# pi_zero.net
KiCad netlist of a schematic drawn in EAGLE
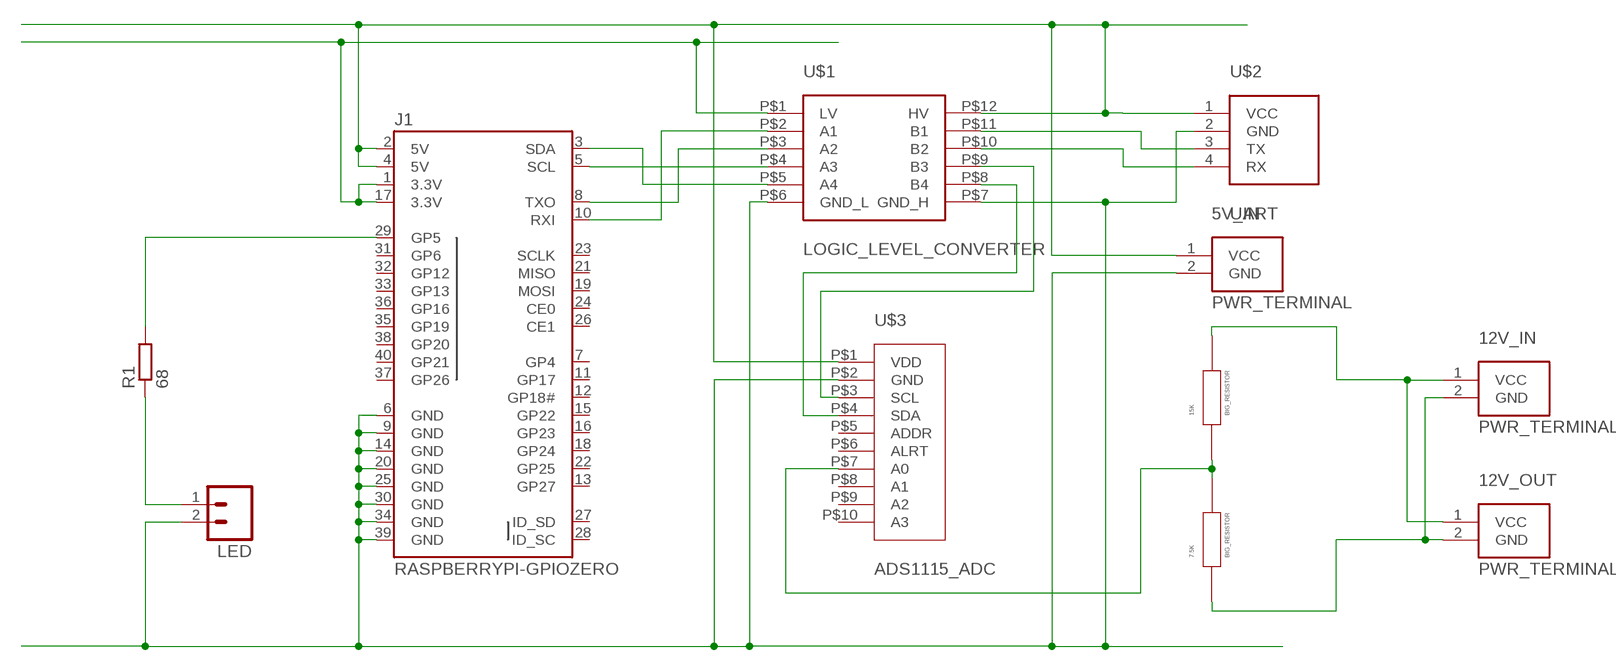
[diagram p0: schematic, sheet 1]

(export (version "E")
  (design (tool "Eeschema 10.0.6"))
  (components
    (comp (ref "5V_IN")
      (value "PWR_TERMINAL")
      (footprint "eagle-import:PWR_TERMINAL")
      (libsource (lib "eagle-import") (part "PWR_TERMINAL"))
    )
    (comp (ref "7.5K")
      (value "BIG_RESISTOR")
      (footprint "eagle-import:BIG_RESISTOR")
      (libsource (lib "eagle-import") (part "BIG_RESISTOR"))
    )
    (comp (ref "12V_IN")
      (value "PWR_TERMINAL")
      (footprint "eagle-import:PWR_TERMINAL")
      (libsource (lib "eagle-import") (part "PWR_TERMINAL"))
    )
    (comp (ref "12V_OUT")
      (value "PWR_TERMINAL")
      (footprint "eagle-import:PWR_TERMINAL")
      (libsource (lib "eagle-import") (part "PWR_TERMINAL"))
    )
    (comp (ref "15K")
      (value "BIG_RESISTOR")
      (footprint "eagle-import:BIG_RESISTOR")
      (libsource (lib "eagle-import") (part "BIG_RESISTOR"))
    )
    (comp (ref "J1")
      (value "RASPBERRYPI-GPIOZERO")
      (footprint "eagle-import:2X20-ZERO")
      (libsource (lib "eagle-import") (part "RASPBERRYPI-GPIOZERO"))
    )
    (comp (ref "LED")
      (value "M02LOCK_LONGPADS")
      (footprint "eagle-import:1X02_LOCK_LONGPADS")
      (libsource (lib "eagle-import") (part "M02LOCK_LONGPADS"))
    )
    (comp (ref "R1")
      (value "68")
      (footprint "eagle-import:0204_7")
      (libsource (lib "eagle-import") (part "R-EU_0204/7"))
    )
    (comp (ref "U$1")
      (value "LOGIC_LEVEL_CONVERTER")
      (footprint "eagle-import:LOGIC_LEVEL_CONVERTER")
      (libsource (lib "eagle-import") (part "LOGIC_LEVEL_CONVERTER"))
    )
    (comp (ref "U$2")
      (value "UART")
      (footprint "eagle-import:I2C_TERM")
      (libsource (lib "eagle-import") (part "UART"))
    )
    (comp (ref "U$3")
      (value "ADS1115_ADC")
      (footprint "eagle-import:ADS1115_ADC")
      (libsource (lib "eagle-import") (part "ADS1115_ADC"))
    )
  )
  (nets
    (net (code "1") (name "Net-(5V_IN-GND)") (class "Default")
      (node (ref "5V_IN") (pin "2") (pinfunction "GND_2") (pintype "bidirectional"))
      (node (ref "J1") (pin "14") (pinfunction "GND_14") (pintype "power_in"))
      (node (ref "J1") (pin "20") (pinfunction "GND_20") (pintype "power_in"))
      (node (ref "J1") (pin "25") (pinfunction "GND_25") (pintype "power_in"))
      (node (ref "J1") (pin "30") (pinfunction "GND_30") (pintype "power_in"))
      (node (ref "J1") (pin "34") (pinfunction "GND_34") (pintype "power_in"))
      (node (ref "J1") (pin "39") (pinfunction "GND_39") (pintype "power_in"))
      (node (ref "J1") (pin "6") (pinfunction "GND_6") (pintype "power_in"))
      (node (ref "J1") (pin "9") (pinfunction "GND_9") (pintype "power_in"))
      (node (ref "LED") (pin "2") (pinfunction "2_2") (pintype "passive"))
      (node (ref "U$1") (pin "P$6") (pinfunction "GND_L_P$6") (pintype "bidirectional"))
      (node (ref "U$1") (pin "P$7") (pinfunction "GND_H_P$7") (pintype "bidirectional"))
      (node (ref "U$2") (pin "2") (pinfunction "GND_2") (pintype "bidirectional"))
      (node (ref "U$3") (pin "P$2") (pinfunction "GND_P$2") (pintype "bidirectional"))
    )
    (net (code "2") (name "Net-(5V_IN-VCC)") (class "Default")
      (node (ref "5V_IN") (pin "1") (pinfunction "VCC_1") (pintype "bidirectional"))
      (node (ref "J1") (pin "2") (pinfunction "5V_2") (pintype "power_in"))
      (node (ref "J1") (pin "4") (pinfunction "5V_4") (pintype "power_in"))
      (node (ref "U$1") (pin "P$12") (pinfunction "HV_P$12") (pintype "bidirectional"))
      (node (ref "U$2") (pin "1") (pinfunction "VCC_1") (pintype "bidirectional"))
      (node (ref "U$3") (pin "P$1") (pinfunction "VDD_P$1") (pintype "bidirectional"))
    )
    (net (code "3") (name "Net-(12V_IN-GND)") (class "Default")
      (node (ref "12V_IN") (pin "2") (pinfunction "GND_2") (pintype "bidirectional"))
      (node (ref "12V_OUT") (pin "2") (pinfunction "GND_2") (pintype "bidirectional"))
      (node (ref "7.5K") (pin "P$1") (pinfunction "P$1_P$1") (pintype "bidirectional"))
    )
    (net (code "4") (name "Net-(12V_IN-VCC)") (class "Default")
      (node (ref "12V_IN") (pin "1") (pinfunction "VCC_1") (pintype "bidirectional"))
      (node (ref "12V_OUT") (pin "1") (pinfunction "VCC_1") (pintype "bidirectional"))
      (node (ref "15K") (pin "P$2") (pinfunction "P$2_P$2") (pintype "bidirectional"))
    )
    (net (code "5") (name "Net-(J1-GP5)") (class "Default")
      (node (ref "J1") (pin "29") (pinfunction "GP5_29") (pintype "bidirectional"))
      (node (ref "R1") (pin "2") (pinfunction "2_2") (pintype "passive"))
    )
    (net (code "6") (name "Net-(J1-RXI)") (class "Default")
      (node (ref "J1") (pin "10") (pinfunction "RXI_10") (pintype "input"))
      (node (ref "U$1") (pin "P$2") (pinfunction "A1_P$2") (pintype "bidirectional"))
    )
    (net (code "7") (name "Net-(J1-SCL)") (class "Default")
      (node (ref "J1") (pin "5") (pinfunction "SCL_5") (pintype "bidirectional"))
      (node (ref "U$1") (pin "P$4") (pinfunction "A3_P$4") (pintype "bidirectional"))
    )
    (net (code "8") (name "Net-(J1-SDA)") (class "Default")
      (node (ref "J1") (pin "3") (pinfunction "SDA_3") (pintype "bidirectional"))
      (node (ref "U$1") (pin "P$5") (pinfunction "A4_P$5") (pintype "bidirectional"))
    )
    (net (code "9") (name "Net-(J1-TXO)") (class "Default")
      (node (ref "J1") (pin "8") (pinfunction "TXO_8") (pintype "output"))
      (node (ref "U$1") (pin "P$3") (pinfunction "A2_P$3") (pintype "bidirectional"))
    )
    (net (code "10") (name "Net-(LED-Pad1)") (class "Default")
      (node (ref "LED") (pin "1") (pinfunction "1_1") (pintype "passive"))
      (node (ref "R1") (pin "1") (pinfunction "1_1") (pintype "passive"))
    )
    (net (code "11") (name "Net-(U$1-B1)") (class "Default")
      (node (ref "U$1") (pin "P$11") (pinfunction "B1_P$11") (pintype "bidirectional"))
      (node (ref "U$2") (pin "3") (pinfunction "TX_3") (pintype "bidirectional"))
    )
    (net (code "12") (name "Net-(U$1-B2)") (class "Default")
      (node (ref "U$1") (pin "P$10") (pinfunction "B2_P$10") (pintype "bidirectional"))
      (node (ref "U$2") (pin "4") (pinfunction "RX_4") (pintype "bidirectional"))
    )
    (net (code "13") (name "Net-(U$1-B3)") (class "Default")
      (node (ref "U$1") (pin "P$9") (pinfunction "B3_P$9") (pintype "bidirectional"))
      (node (ref "U$3") (pin "P$3") (pinfunction "SCL_P$3") (pintype "bidirectional"))
    )
    (net (code "14") (name "Net-(U$1-B4)") (class "Default")
      (node (ref "U$1") (pin "P$8") (pinfunction "B4_P$8") (pintype "bidirectional"))
      (node (ref "U$3") (pin "P$4") (pinfunction "SDA_P$4") (pintype "bidirectional"))
    )
    (net (code "15") (name "Net-(U$1-LV)") (class "Default")
      (node (ref "J1") (pin "1") (pinfunction "3.3V_1") (pintype "power_in"))
      (node (ref "J1") (pin "17") (pinfunction "3.3V_17") (pintype "power_in"))
      (node (ref "U$1") (pin "P$1") (pinfunction "LV_P$1") (pintype "bidirectional"))
    )
    (net (code "16") (name "Net-(U$3-A0)") (class "Default")
      (node (ref "15K") (pin "P$1") (pinfunction "P$1_P$1") (pintype "bidirectional"))
      (node (ref "7.5K") (pin "P$2") (pinfunction "P$2_P$2") (pintype "bidirectional"))
      (node (ref "U$3") (pin "P$7") (pinfunction "A0_P$7") (pintype "bidirectional"))
    )
    (net (code "17") (name "unconnected-(J1-CE0-Pad24)") (class "Default")
      (node (ref "J1") (pin "24") (pinfunction "CE0_24") (pintype "output"))
    )
    (net (code "18") (name "unconnected-(J1-CE1-Pad26)") (class "Default")
      (node (ref "J1") (pin "26") (pinfunction "CE1_26") (pintype "output"))
    )
    (net (code "19") (name "unconnected-(J1-GP4-Pad7)") (class "Default")
      (node (ref "J1") (pin "7") (pinfunction "GP4_7") (pintype "bidirectional"))
    )
    (net (code "20") (name "unconnected-(J1-GP6-Pad31)") (class "Default")
      (node (ref "J1") (pin "31") (pinfunction "GP6_31") (pintype "bidirectional"))
    )
    (net (code "21") (name "unconnected-(J1-GP12-Pad32)") (class "Default")
      (node (ref "J1") (pin "32") (pinfunction "GP12_32") (pintype "bidirectional"))
    )
    (net (code "22") (name "unconnected-(J1-GP13-Pad33)") (class "Default")
      (node (ref "J1") (pin "33") (pinfunction "GP13_33") (pintype "bidirectional"))
    )
    (net (code "23") (name "unconnected-(J1-GP16-Pad36)") (class "Default")
      (node (ref "J1") (pin "36") (pinfunction "GP16_36") (pintype "bidirectional"))
    )
    (net (code "24") (name "unconnected-(J1-GP17-Pad11)") (class "Default")
      (node (ref "J1") (pin "11") (pinfunction "GP17_11") (pintype "bidirectional"))
    )
    (net (code "25") (name "unconnected-(J1-GP18#-Pad12)") (class "Default")
      (node (ref "J1") (pin "12") (pinfunction "GP18#_12") (pintype "bidirectional"))
    )
    (net (code "26") (name "unconnected-(J1-GP19-Pad35)") (class "Default")
      (node (ref "J1") (pin "35") (pinfunction "GP19_35") (pintype "bidirectional"))
    )
    (net (code "27") (name "unconnected-(J1-GP20-Pad38)") (class "Default")
      (node (ref "J1") (pin "38") (pinfunction "GP20_38") (pintype "bidirectional"))
    )
    (net (code "28") (name "unconnected-(J1-GP21-Pad40)") (class "Default")
      (node (ref "J1") (pin "40") (pinfunction "GP21_40") (pintype "bidirectional"))
    )
    (net (code "29") (name "unconnected-(J1-GP22-Pad15)") (class "Default")
      (node (ref "J1") (pin "15") (pinfunction "GP22_15") (pintype "bidirectional"))
    )
    (net (code "30") (name "unconnected-(J1-GP23-Pad16)") (class "Default")
      (node (ref "J1") (pin "16") (pinfunction "GP23_16") (pintype "bidirectional"))
    )
    (net (code "31") (name "unconnected-(J1-GP24-Pad18)") (class "Default")
      (node (ref "J1") (pin "18") (pinfunction "GP24_18") (pintype "bidirectional"))
    )
    (net (code "32") (name "unconnected-(J1-GP25-Pad22)") (class "Default")
      (node (ref "J1") (pin "22") (pinfunction "GP25_22") (pintype "bidirectional"))
    )
    (net (code "33") (name "unconnected-(J1-GP26-Pad37)") (class "Default")
      (node (ref "J1") (pin "37") (pinfunction "GP26_37") (pintype "bidirectional"))
    )
    (net (code "34") (name "unconnected-(J1-GP27-Pad13)") (class "Default")
      (node (ref "J1") (pin "13") (pinfunction "GP27_13") (pintype "bidirectional"))
    )
    (net (code "35") (name "unconnected-(J1-ID_SC-Pad28)") (class "Default")
      (node (ref "J1") (pin "28") (pinfunction "ID_SC_28") (pintype "bidirectional"))
    )
    (net (code "36") (name "unconnected-(J1-ID_SD-Pad27)") (class "Default")
      (node (ref "J1") (pin "27") (pinfunction "ID_SD_27") (pintype "bidirectional"))
    )
    (net (code "37") (name "unconnected-(J1-MISO-Pad21)") (class "Default")
      (node (ref "J1") (pin "21") (pinfunction "MISO_21") (pintype "input"))
    )
    (net (code "38") (name "unconnected-(J1-MOSI-Pad19)") (class "Default")
      (node (ref "J1") (pin "19") (pinfunction "MOSI_19") (pintype "output"))
    )
    (net (code "39") (name "unconnected-(J1-SCLK-Pad23)") (class "Default")
      (node (ref "J1") (pin "23") (pinfunction "SCLK_23") (pintype "output"))
    )
    (net (code "40") (name "unconnected-(U$3-A1-PadP$8)") (class "Default")
      (node (ref "U$3") (pin "P$8") (pinfunction "A1_P$8") (pintype "bidirectional"))
    )
    (net (code "41") (name "unconnected-(U$3-A2-PadP$9)") (class "Default")
      (node (ref "U$3") (pin "P$9") (pinfunction "A2_P$9") (pintype "bidirectional"))
    )
    (net (code "42") (name "unconnected-(U$3-A3-PadP$10)") (class "Default")
      (node (ref "U$3") (pin "P$10") (pinfunction "A3_P$10") (pintype "bidirectional"))
    )
    (net (code "43") (name "unconnected-(U$3-ADDR-PadP$5)") (class "Default")
      (node (ref "U$3") (pin "P$5") (pinfunction "ADDR_P$5") (pintype "bidirectional"))
    )
    (net (code "44") (name "unconnected-(U$3-ALRT-PadP$6)") (class "Default")
      (node (ref "U$3") (pin "P$6") (pinfunction "ALRT_P$6") (pintype "bidirectional"))
    )
  )
)
